# logic_gates_cmos.net
KiCad netlist of a schematic drawn in EAGLE
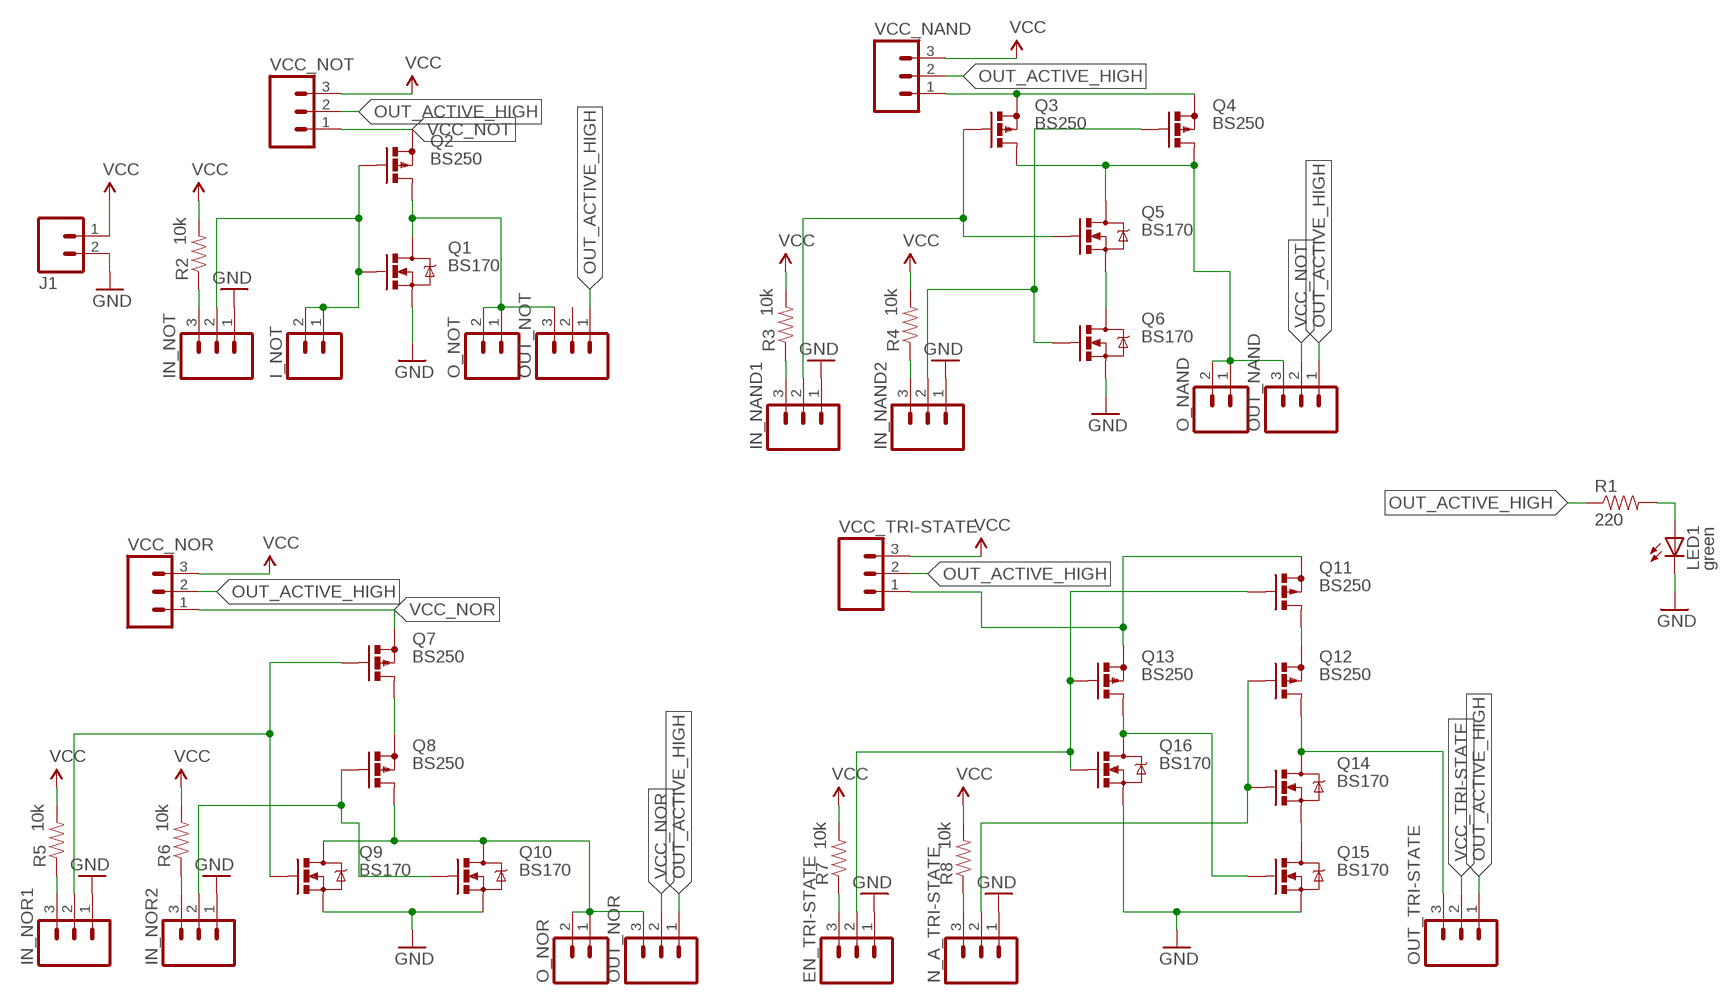
[diagram p0: schematic, sheet 1]

(export (version "E")
  (design (tool "Eeschema 10.0.6"))
  (components
    (comp (ref "EN_TRI-STATE")
      (value "M03LONGPADS")
      (footprint "eagle-import:1X03_LONGPADS")
      (libsource (lib "eagle-import") (part "M03LONGPADS"))
    )
    (comp (ref "IN_NAND1")
      (value "M03LONGPADS")
      (footprint "eagle-import:1X03_LONGPADS")
      (libsource (lib "eagle-import") (part "M03LONGPADS"))
    )
    (comp (ref "IN_NAND2")
      (value "M03LONGPADS")
      (footprint "eagle-import:1X03_LONGPADS")
      (libsource (lib "eagle-import") (part "M03LONGPADS"))
    )
    (comp (ref "IN_NOR1")
      (value "M03LONGPADS")
      (footprint "eagle-import:1X03_LONGPADS")
      (libsource (lib "eagle-import") (part "M03LONGPADS"))
    )
    (comp (ref "IN_NOR2")
      (value "M03LONGPADS")
      (footprint "eagle-import:1X03_LONGPADS")
      (libsource (lib "eagle-import") (part "M03LONGPADS"))
    )
    (comp (ref "IN_NOT")
      (value "M03LONGPADS")
      (footprint "eagle-import:1X03_LONGPADS")
      (libsource (lib "eagle-import") (part "M03LONGPADS"))
    )
    (comp (ref "I_NOT")
      (value "M02PTH")
      (footprint "eagle-import:1X02")
      (libsource (lib "eagle-import") (part "M02PTH"))
    )
    (comp (ref "J1")
      (value "M02LOCK_LONGPADS")
      (footprint "eagle-import:1X02_LOCK_LONGPADS")
      (libsource (lib "eagle-import") (part "M02LOCK_LONGPADS"))
    )
    (comp (ref "LED1")
      (value "green")
      (footprint "eagle-import:LED3MM")
      (libsource (lib "eagle-import") (part "LED3MM"))
    )
    (comp (ref "N_A_TRI-STATE")
      (value "M03LONGPADS")
      (footprint "eagle-import:1X03_LONGPADS")
      (libsource (lib "eagle-import") (part "M03LONGPADS"))
    )
    (comp (ref "OUT_NAND")
      (value "M03LONGPADS")
      (footprint "eagle-import:1X03_LONGPADS")
      (libsource (lib "eagle-import") (part "M03LONGPADS"))
    )
    (comp (ref "OUT_NOR")
      (value "M03LONGPADS")
      (footprint "eagle-import:1X03_LONGPADS")
      (libsource (lib "eagle-import") (part "M03LONGPADS"))
    )
    (comp (ref "OUT_NOT")
      (value "M03LONGPADS")
      (footprint "eagle-import:1X03_LONGPADS")
      (libsource (lib "eagle-import") (part "M03LONGPADS"))
    )
    (comp (ref "OUT_TRI-STATE")
      (value "M03LONGPADS")
      (footprint "eagle-import:1X03_LONGPADS")
      (libsource (lib "eagle-import") (part "M03LONGPADS"))
    )
    (comp (ref "O_NAND")
      (value "M02PTH")
      (footprint "eagle-import:1X02")
      (libsource (lib "eagle-import") (part "M02PTH"))
    )
    (comp (ref "O_NOR")
      (value "M02PTH")
      (footprint "eagle-import:1X02")
      (libsource (lib "eagle-import") (part "M02PTH"))
    )
    (comp (ref "O_NOT")
      (value "M02PTH")
      (footprint "eagle-import:1X02")
      (libsource (lib "eagle-import") (part "M02PTH"))
    )
    (comp (ref "Q1")
      (value "BS170")
      (footprint "eagle-import:TO92-OVAL")
      (libsource (lib "eagle-import") (part "BS170_LP"))
    )
    (comp (ref "Q2")
      (value "BS250")
      (footprint "eagle-import:TO92-OVAL")
      (libsource (lib "eagle-import") (part "PFETBS250"))
    )
    (comp (ref "Q3")
      (value "BS250")
      (footprint "eagle-import:TO92-OVAL")
      (libsource (lib "eagle-import") (part "PFETBS250"))
    )
    (comp (ref "Q4")
      (value "BS250")
      (footprint "eagle-import:TO92-OVAL")
      (libsource (lib "eagle-import") (part "PFETBS250"))
    )
    (comp (ref "Q5")
      (value "BS170")
      (footprint "eagle-import:TO92-OVAL")
      (libsource (lib "eagle-import") (part "BS170_LP"))
    )
    (comp (ref "Q6")
      (value "BS170")
      (footprint "eagle-import:TO92-OVAL")
      (libsource (lib "eagle-import") (part "BS170_LP"))
    )
    (comp (ref "Q7")
      (value "BS250")
      (footprint "eagle-import:TO92-OVAL")
      (libsource (lib "eagle-import") (part "PFETBS250"))
    )
    (comp (ref "Q8")
      (value "BS250")
      (footprint "eagle-import:TO92-OVAL")
      (libsource (lib "eagle-import") (part "PFETBS250"))
    )
    (comp (ref "Q9")
      (value "BS170")
      (footprint "eagle-import:TO92-OVAL")
      (libsource (lib "eagle-import") (part "BS170_LP"))
    )
    (comp (ref "Q10")
      (value "BS170")
      (footprint "eagle-import:TO92-OVAL")
      (libsource (lib "eagle-import") (part "BS170_LP"))
    )
    (comp (ref "Q11")
      (value "BS250")
      (footprint "eagle-import:TO92-OVAL")
      (libsource (lib "eagle-import") (part "PFETBS250"))
    )
    (comp (ref "Q12")
      (value "BS250")
      (footprint "eagle-import:TO92-OVAL")
      (libsource (lib "eagle-import") (part "PFETBS250"))
    )
    (comp (ref "Q13")
      (value "BS250")
      (footprint "eagle-import:TO92-OVAL")
      (libsource (lib "eagle-import") (part "PFETBS250"))
    )
    (comp (ref "Q14")
      (value "BS170")
      (footprint "eagle-import:TO92-OVAL")
      (libsource (lib "eagle-import") (part "BS170_LP"))
    )
    (comp (ref "Q15")
      (value "BS170")
      (footprint "eagle-import:TO92-OVAL")
      (libsource (lib "eagle-import") (part "BS170_LP"))
    )
    (comp (ref "Q16")
      (value "BS170")
      (footprint "eagle-import:TO92-OVAL")
      (libsource (lib "eagle-import") (part "BS170_LP"))
    )
    (comp (ref "R1")
      (value "220")
      (footprint "eagle-import:AXIAL-0.4")
      (libsource (lib "eagle-import") (part "RESISTORPTH-1/4W"))
    )
    (comp (ref "R2")
      (value "10k")
      (footprint "eagle-import:AXIAL-0.4")
      (libsource (lib "eagle-import") (part "RESISTORPTH-1/4W"))
    )
    (comp (ref "R3")
      (value "10k")
      (footprint "eagle-import:AXIAL-0.4")
      (libsource (lib "eagle-import") (part "RESISTORPTH-1/4W"))
    )
    (comp (ref "R4")
      (value "10k")
      (footprint "eagle-import:AXIAL-0.4")
      (libsource (lib "eagle-import") (part "RESISTORPTH-1/4W"))
    )
    (comp (ref "R5")
      (value "10k")
      (footprint "eagle-import:AXIAL-0.4")
      (libsource (lib "eagle-import") (part "RESISTORPTH-1/4W"))
    )
    (comp (ref "R6")
      (value "10k")
      (footprint "eagle-import:AXIAL-0.4")
      (libsource (lib "eagle-import") (part "RESISTORPTH-1/4W"))
    )
    (comp (ref "R7")
      (value "10k")
      (footprint "eagle-import:AXIAL-0.4")
      (libsource (lib "eagle-import") (part "RESISTORPTH-1/4W"))
    )
    (comp (ref "R8")
      (value "10k")
      (footprint "eagle-import:AXIAL-0.4")
      (libsource (lib "eagle-import") (part "RESISTORPTH-1/4W"))
    )
    (comp (ref "VCC_NAND")
      (value "M03LONGPADS")
      (footprint "eagle-import:1X03_LONGPADS")
      (libsource (lib "eagle-import") (part "M03LONGPADS"))
    )
    (comp (ref "VCC_NOR")
      (value "M03LONGPADS")
      (footprint "eagle-import:1X03_LONGPADS")
      (libsource (lib "eagle-import") (part "M03LONGPADS"))
    )
    (comp (ref "VCC_NOT")
      (value "M03LONGPADS")
      (footprint "eagle-import:1X03_LONGPADS")
      (libsource (lib "eagle-import") (part "M03LONGPADS"))
    )
    (comp (ref "VCC_TRI-STATE")
      (value "M03LONGPADS")
      (footprint "eagle-import:1X03_LONGPADS")
      (libsource (lib "eagle-import") (part "M03LONGPADS"))
    )
  )
  (nets
    (net (code "1") (name "GND") (class "Default")
      (node (ref "EN_TRI-STATE") (pin "1") (pinfunction "1_1") (pintype "passive"))
      (node (ref "IN_NAND1") (pin "1") (pinfunction "1_1") (pintype "passive"))
      (node (ref "IN_NAND2") (pin "1") (pinfunction "1_1") (pintype "passive"))
      (node (ref "IN_NOR1") (pin "1") (pinfunction "1_1") (pintype "passive"))
      (node (ref "IN_NOR2") (pin "1") (pinfunction "1_1") (pintype "passive"))
      (node (ref "IN_NOT") (pin "1") (pinfunction "1_1") (pintype "passive"))
      (node (ref "J1") (pin "2") (pinfunction "2_2") (pintype "passive"))
      (node (ref "LED1") (pin "K") (pinfunction "C_K") (pintype "passive"))
      (node (ref "N_A_TRI-STATE") (pin "1") (pinfunction "1_1") (pintype "passive"))
      (node (ref "Q1") (pin "3") (pinfunction "S_3") (pintype "passive"))
      (node (ref "Q10") (pin "3") (pinfunction "S_3") (pintype "passive"))
      (node (ref "Q15") (pin "3") (pinfunction "S_3") (pintype "passive"))
      (node (ref "Q16") (pin "3") (pinfunction "S_3") (pintype "passive"))
      (node (ref "Q6") (pin "3") (pinfunction "S_3") (pintype "passive"))
      (node (ref "Q9") (pin "3") (pinfunction "S_3") (pintype "passive"))
    )
    (net (code "2") (name "Net-(Q1-D)") (class "Default")
      (node (ref "OUT_NOT") (pin "3") (pinfunction "3_3") (pintype "passive"))
      (node (ref "O_NOT") (pin "1") (pinfunction "1_1") (pintype "passive"))
      (node (ref "O_NOT") (pin "2") (pinfunction "2_2") (pintype "passive"))
      (node (ref "Q1") (pin "1") (pinfunction "D_1") (pintype "passive"))
      (node (ref "Q2") (pin "1") (pinfunction "D_1") (pintype "passive"))
    )
    (net (code "3") (name "Net-(Q1-G)") (class "Default")
      (node (ref "IN_NOT") (pin "2") (pinfunction "2_2") (pintype "passive"))
      (node (ref "I_NOT") (pin "1") (pinfunction "1_1") (pintype "passive"))
      (node (ref "I_NOT") (pin "2") (pinfunction "2_2") (pintype "passive"))
      (node (ref "Q1") (pin "2") (pinfunction "G_2") (pintype "passive"))
      (node (ref "Q2") (pin "2") (pinfunction "G_2") (pintype "passive"))
    )
    (net (code "4") (name "Net-(Q3-D)") (class "Default")
      (node (ref "OUT_NAND") (pin "3") (pinfunction "3_3") (pintype "passive"))
      (node (ref "O_NAND") (pin "1") (pinfunction "1_1") (pintype "passive"))
      (node (ref "O_NAND") (pin "2") (pinfunction "2_2") (pintype "passive"))
      (node (ref "Q3") (pin "1") (pinfunction "D_1") (pintype "passive"))
      (node (ref "Q4") (pin "1") (pinfunction "D_1") (pintype "passive"))
      (node (ref "Q5") (pin "1") (pinfunction "D_1") (pintype "passive"))
    )
    (net (code "5") (name "Net-(Q3-G)") (class "Default")
      (node (ref "IN_NAND1") (pin "2") (pinfunction "2_2") (pintype "passive"))
      (node (ref "Q3") (pin "2") (pinfunction "G_2") (pintype "passive"))
      (node (ref "Q5") (pin "2") (pinfunction "G_2") (pintype "passive"))
    )
    (net (code "6") (name "Net-(Q3-S)") (class "Default")
      (node (ref "Q3") (pin "3") (pinfunction "S_3") (pintype "passive"))
      (node (ref "Q4") (pin "3") (pinfunction "S_3") (pintype "passive"))
      (node (ref "VCC_NAND") (pin "1") (pinfunction "1_1") (pintype "passive"))
    )
    (net (code "7") (name "Net-(Q4-G)") (class "Default")
      (node (ref "IN_NAND2") (pin "2") (pinfunction "2_2") (pintype "passive"))
      (node (ref "Q4") (pin "2") (pinfunction "G_2") (pintype "passive"))
      (node (ref "Q6") (pin "2") (pinfunction "G_2") (pintype "passive"))
    )
    (net (code "8") (name "Net-(Q5-S)") (class "Default")
      (node (ref "Q5") (pin "3") (pinfunction "S_3") (pintype "passive"))
      (node (ref "Q6") (pin "1") (pinfunction "D_1") (pintype "passive"))
    )
    (net (code "9") (name "Net-(Q7-D)") (class "Default")
      (node (ref "Q7") (pin "1") (pinfunction "D_1") (pintype "passive"))
      (node (ref "Q8") (pin "3") (pinfunction "S_3") (pintype "passive"))
    )
    (net (code "10") (name "Net-(Q7-G)") (class "Default")
      (node (ref "IN_NOR1") (pin "2") (pinfunction "2_2") (pintype "passive"))
      (node (ref "Q7") (pin "2") (pinfunction "G_2") (pintype "passive"))
      (node (ref "Q9") (pin "2") (pinfunction "G_2") (pintype "passive"))
    )
    (net (code "11") (name "Net-(Q10-D)") (class "Default")
      (node (ref "OUT_NOR") (pin "3") (pinfunction "3_3") (pintype "passive"))
      (node (ref "O_NOR") (pin "1") (pinfunction "1_1") (pintype "passive"))
      (node (ref "O_NOR") (pin "2") (pinfunction "2_2") (pintype "passive"))
      (node (ref "Q10") (pin "1") (pinfunction "D_1") (pintype "passive"))
      (node (ref "Q8") (pin "1") (pinfunction "D_1") (pintype "passive"))
      (node (ref "Q9") (pin "1") (pinfunction "D_1") (pintype "passive"))
    )
    (net (code "12") (name "Net-(Q10-G)") (class "Default")
      (node (ref "IN_NOR2") (pin "2") (pinfunction "2_2") (pintype "passive"))
      (node (ref "Q10") (pin "2") (pinfunction "G_2") (pintype "passive"))
      (node (ref "Q8") (pin "2") (pinfunction "G_2") (pintype "passive"))
    )
    (net (code "13") (name "Net-(Q11-D)") (class "Default")
      (node (ref "Q11") (pin "1") (pinfunction "D_1") (pintype "passive"))
      (node (ref "Q12") (pin "3") (pinfunction "S_3") (pintype "passive"))
    )
    (net (code "14") (name "Net-(Q11-G)") (class "Default")
      (node (ref "EN_TRI-STATE") (pin "2") (pinfunction "2_2") (pintype "passive"))
      (node (ref "Q11") (pin "2") (pinfunction "G_2") (pintype "passive"))
      (node (ref "Q13") (pin "2") (pinfunction "G_2") (pintype "passive"))
      (node (ref "Q16") (pin "2") (pinfunction "G_2") (pintype "passive"))
    )
    (net (code "15") (name "Net-(Q12-D)") (class "Default")
      (node (ref "OUT_TRI-STATE") (pin "3") (pinfunction "3_3") (pintype "passive"))
      (node (ref "Q12") (pin "1") (pinfunction "D_1") (pintype "passive"))
      (node (ref "Q14") (pin "1") (pinfunction "D_1") (pintype "passive"))
    )
    (net (code "16") (name "Net-(Q12-G)") (class "Default")
      (node (ref "N_A_TRI-STATE") (pin "2") (pinfunction "2_2") (pintype "passive"))
      (node (ref "Q12") (pin "2") (pinfunction "G_2") (pintype "passive"))
      (node (ref "Q14") (pin "2") (pinfunction "G_2") (pintype "passive"))
    )
    (net (code "17") (name "Net-(Q13-D)") (class "Default")
      (node (ref "Q13") (pin "1") (pinfunction "D_1") (pintype "passive"))
      (node (ref "Q15") (pin "2") (pinfunction "G_2") (pintype "passive"))
      (node (ref "Q16") (pin "1") (pinfunction "D_1") (pintype "passive"))
    )
    (net (code "18") (name "Net-(Q14-S)") (class "Default")
      (node (ref "Q14") (pin "3") (pinfunction "S_3") (pintype "passive"))
      (node (ref "Q15") (pin "1") (pinfunction "D_1") (pintype "passive"))
    )
    (net (code "19") (name "Net-(R1-2)") (class "Default")
      (node (ref "LED1") (pin "A") (pinfunction "A_A") (pintype "passive"))
      (node (ref "R1") (pin "P$2") (pinfunction "2_P$2") (pintype "passive"))
    )
    (net (code "20") (name "Net-(R2-1)") (class "Default")
      (node (ref "IN_NOT") (pin "3") (pinfunction "3_3") (pintype "passive"))
      (node (ref "R2") (pin "P$1") (pinfunction "1_P$1") (pintype "passive"))
    )
    (net (code "21") (name "Net-(R3-1)") (class "Default")
      (node (ref "IN_NAND1") (pin "3") (pinfunction "3_3") (pintype "passive"))
      (node (ref "R3") (pin "P$1") (pinfunction "1_P$1") (pintype "passive"))
    )
    (net (code "22") (name "Net-(R4-1)") (class "Default")
      (node (ref "IN_NAND2") (pin "3") (pinfunction "3_3") (pintype "passive"))
      (node (ref "R4") (pin "P$1") (pinfunction "1_P$1") (pintype "passive"))
    )
    (net (code "23") (name "Net-(R5-1)") (class "Default")
      (node (ref "IN_NOR1") (pin "3") (pinfunction "3_3") (pintype "passive"))
      (node (ref "R5") (pin "P$1") (pinfunction "1_P$1") (pintype "passive"))
    )
    (net (code "24") (name "Net-(R6-1)") (class "Default")
      (node (ref "IN_NOR2") (pin "3") (pinfunction "3_3") (pintype "passive"))
      (node (ref "R6") (pin "P$1") (pinfunction "1_P$1") (pintype "passive"))
    )
    (net (code "25") (name "Net-(R7-1)") (class "Default")
      (node (ref "EN_TRI-STATE") (pin "3") (pinfunction "3_3") (pintype "passive"))
      (node (ref "R7") (pin "P$1") (pinfunction "1_P$1") (pintype "passive"))
    )
    (net (code "26") (name "Net-(R8-1)") (class "Default")
      (node (ref "N_A_TRI-STATE") (pin "3") (pinfunction "3_3") (pintype "passive"))
      (node (ref "R8") (pin "P$1") (pinfunction "1_P$1") (pintype "passive"))
    )
    (net (code "27") (name "OUT_ACTIVE_HIGH") (class "Default")
      (node (ref "OUT_NAND") (pin "1") (pinfunction "1_1") (pintype "passive"))
      (node (ref "OUT_NOR") (pin "1") (pinfunction "1_1") (pintype "passive"))
      (node (ref "OUT_NOT") (pin "1") (pinfunction "1_1") (pintype "passive"))
      (node (ref "OUT_TRI-STATE") (pin "1") (pinfunction "1_1") (pintype "passive"))
      (node (ref "R1") (pin "P$1") (pinfunction "1_P$1") (pintype "passive"))
      (node (ref "VCC_NAND") (pin "2") (pinfunction "2_2") (pintype "passive"))
      (node (ref "VCC_NOR") (pin "2") (pinfunction "2_2") (pintype "passive"))
      (node (ref "VCC_NOT") (pin "2") (pinfunction "2_2") (pintype "passive"))
      (node (ref "VCC_TRI-STATE") (pin "2") (pinfunction "2_2") (pintype "passive"))
    )
    (net (code "28") (name "VCC") (class "Default")
      (node (ref "J1") (pin "1") (pinfunction "1_1") (pintype "passive"))
      (node (ref "R2") (pin "P$2") (pinfunction "2_P$2") (pintype "passive"))
      (node (ref "R3") (pin "P$2") (pinfunction "2_P$2") (pintype "passive"))
      (node (ref "R4") (pin "P$2") (pinfunction "2_P$2") (pintype "passive"))
      (node (ref "R5") (pin "P$2") (pinfunction "2_P$2") (pintype "passive"))
      (node (ref "R6") (pin "P$2") (pinfunction "2_P$2") (pintype "passive"))
      (node (ref "R7") (pin "P$2") (pinfunction "2_P$2") (pintype "passive"))
      (node (ref "R8") (pin "P$2") (pinfunction "2_P$2") (pintype "passive"))
      (node (ref "VCC_NAND") (pin "3") (pinfunction "3_3") (pintype "passive"))
      (node (ref "VCC_NOR") (pin "3") (pinfunction "3_3") (pintype "passive"))
      (node (ref "VCC_NOT") (pin "3") (pinfunction "3_3") (pintype "passive"))
      (node (ref "VCC_TRI-STATE") (pin "3") (pinfunction "3_3") (pintype "passive"))
    )
    (net (code "29") (name "VCC_NOR") (class "Default")
      (node (ref "OUT_NOR") (pin "2") (pinfunction "2_2") (pintype "passive"))
      (node (ref "Q7") (pin "3") (pinfunction "S_3") (pintype "passive"))
      (node (ref "VCC_NOR") (pin "1") (pinfunction "1_1") (pintype "passive"))
    )
    (net (code "30") (name "VCC_NOT") (class "Default")
      (node (ref "OUT_NAND") (pin "2") (pinfunction "2_2") (pintype "passive"))
      (node (ref "Q2") (pin "3") (pinfunction "S_3") (pintype "passive"))
      (node (ref "VCC_NOT") (pin "1") (pinfunction "1_1") (pintype "passive"))
    )
    (net (code "31") (name "VCC_TRI-STATE") (class "Default")
      (node (ref "OUT_TRI-STATE") (pin "2") (pinfunction "2_2") (pintype "passive"))
      (node (ref "Q11") (pin "3") (pinfunction "S_3") (pintype "passive"))
      (node (ref "Q13") (pin "3") (pinfunction "S_3") (pintype "passive"))
      (node (ref "VCC_TRI-STATE") (pin "1") (pinfunction "1_1") (pintype "passive"))
    )
    (net (code "32") (name "unconnected-(OUT_NOT-Pad2)") (class "Default")
      (node (ref "OUT_NOT") (pin "2") (pinfunction "2_2") (pintype "passive"))
    )
  )
)
